# LED_Heart.net
KiCad netlist of a schematic drawn in EAGLE
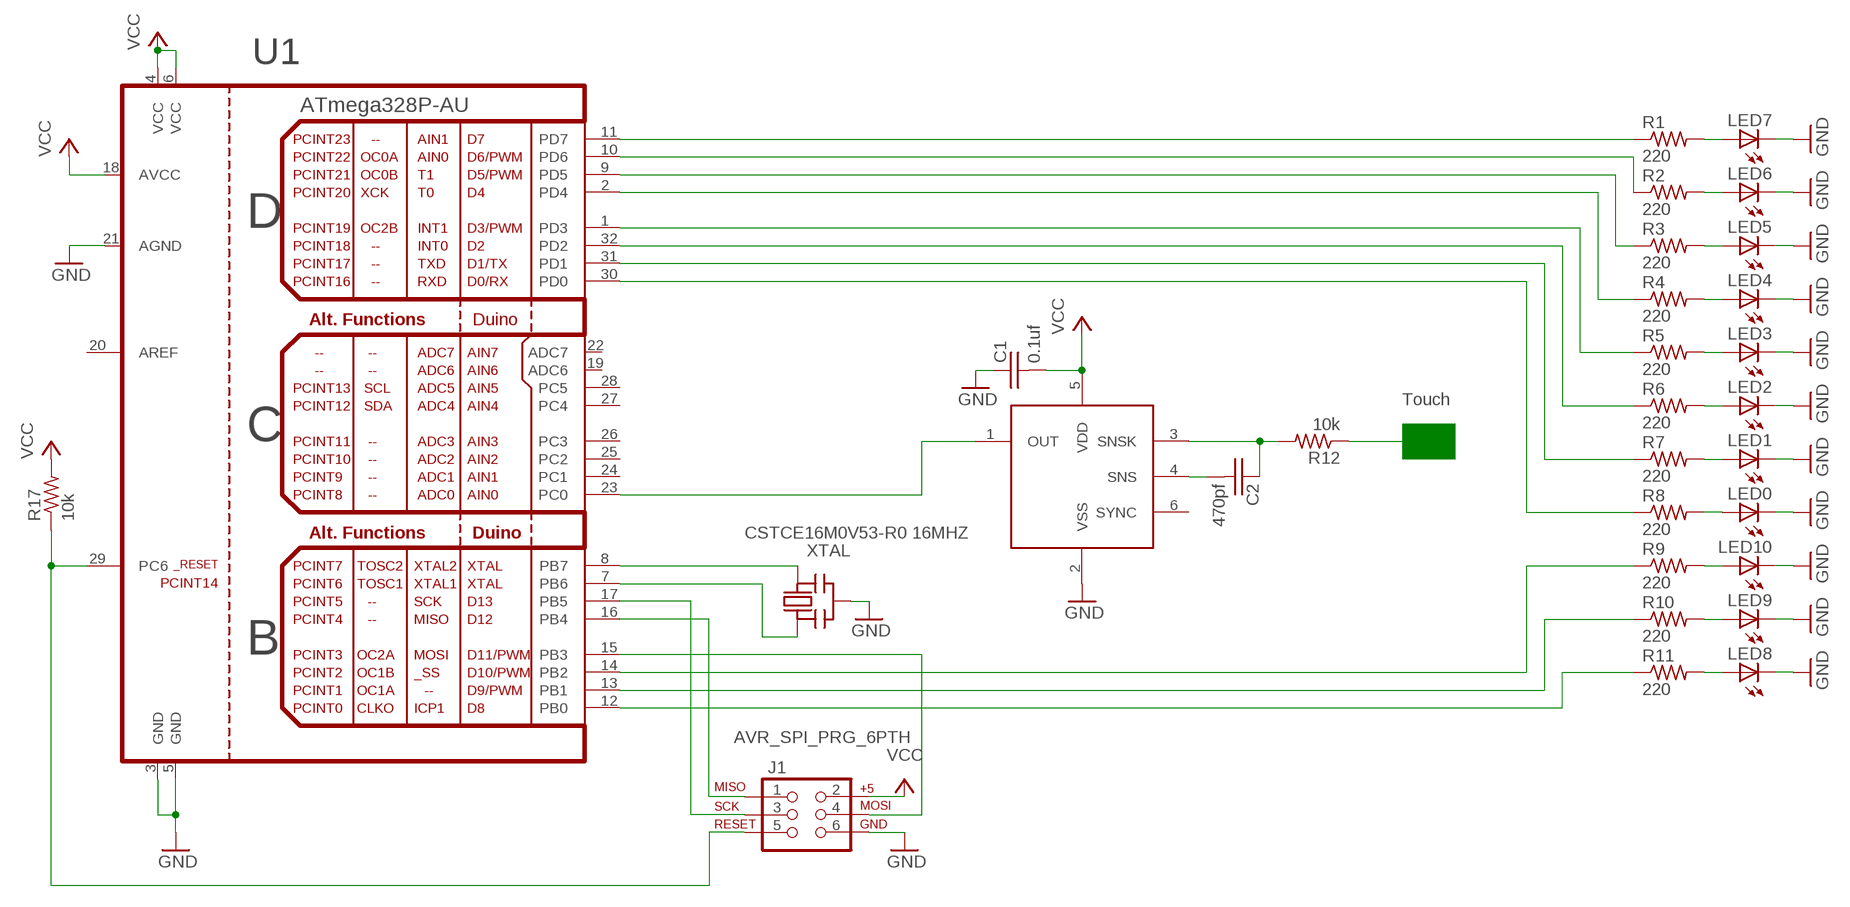
[diagram p0: schematic, sheet 1]

(export (version "E")
  (design (tool "Eeschema 10.0.6"))
  (components
    (comp (ref "C1")
      (value "0.1uf")
      (footprint "eagle-import:C0603")
      (libsource (lib "eagle-import") (part "C-USC0603"))
    )
    (comp (ref "C2")
      (value "470pf")
      (footprint "eagle-import:C0603")
      (libsource (lib "eagle-import") (part "C-USC0603"))
    )
    (comp (ref "J1")
      (value "AVR_SPI_PRG_6PTH")
      (footprint "eagle-import:2X3")
      (libsource (lib "eagle-import") (part "AVR_SPI_PRG_6PTH"))
    )
    (comp (ref "LED0")
      (value "LED0603")
      (footprint "eagle-import:LED-0603")
      (libsource (lib "eagle-import") (part "LED0603"))
    )
    (comp (ref "LED1")
      (value "LED0603")
      (footprint "eagle-import:LED-0603")
      (libsource (lib "eagle-import") (part "LED0603"))
    )
    (comp (ref "LED2")
      (value "LED0603")
      (footprint "eagle-import:LED-0603")
      (libsource (lib "eagle-import") (part "LED0603"))
    )
    (comp (ref "LED3")
      (value "LED0603")
      (footprint "eagle-import:LED-0603")
      (libsource (lib "eagle-import") (part "LED0603"))
    )
    (comp (ref "LED4")
      (value "LED0603")
      (footprint "eagle-import:LED-0603")
      (libsource (lib "eagle-import") (part "LED0603"))
    )
    (comp (ref "LED5")
      (value "LED0603")
      (footprint "eagle-import:LED-0603")
      (libsource (lib "eagle-import") (part "LED0603"))
    )
    (comp (ref "LED6")
      (value "LED0603")
      (footprint "eagle-import:LED-0603")
      (libsource (lib "eagle-import") (part "LED0603"))
    )
    (comp (ref "LED7")
      (value "LED0603")
      (footprint "eagle-import:LED-0603")
      (libsource (lib "eagle-import") (part "LED0603"))
    )
    (comp (ref "LED8")
      (value "LED0603")
      (footprint "eagle-import:LED-0603")
      (libsource (lib "eagle-import") (part "LED0603"))
    )
    (comp (ref "LED9")
      (value "LED0603")
      (footprint "eagle-import:LED-0603")
      (libsource (lib "eagle-import") (part "LED0603"))
    )
    (comp (ref "LED10")
      (value "LED0603")
      (footprint "eagle-import:LED-0603")
      (libsource (lib "eagle-import") (part "LED0603"))
    )
    (comp (ref "R1")
      (value "220")
      (footprint "eagle-import:R0402")
      (libsource (lib "eagle-import") (part "R-US_R0402"))
    )
    (comp (ref "R2")
      (value "220")
      (footprint "eagle-import:R0402")
      (libsource (lib "eagle-import") (part "R-US_R0402"))
    )
    (comp (ref "R3")
      (value "220")
      (footprint "eagle-import:R0402")
      (libsource (lib "eagle-import") (part "R-US_R0402"))
    )
    (comp (ref "R4")
      (value "220")
      (footprint "eagle-import:R0402")
      (libsource (lib "eagle-import") (part "R-US_R0402"))
    )
    (comp (ref "R5")
      (value "220")
      (footprint "eagle-import:R0402")
      (libsource (lib "eagle-import") (part "R-US_R0402"))
    )
    (comp (ref "R6")
      (value "220")
      (footprint "eagle-import:R0402")
      (libsource (lib "eagle-import") (part "R-US_R0402"))
    )
    (comp (ref "R7")
      (value "220")
      (footprint "eagle-import:R0402")
      (libsource (lib "eagle-import") (part "R-US_R0402"))
    )
    (comp (ref "R8")
      (value "220")
      (footprint "eagle-import:R0402")
      (libsource (lib "eagle-import") (part "R-US_R0402"))
    )
    (comp (ref "R9")
      (value "220")
      (footprint "eagle-import:R0402")
      (libsource (lib "eagle-import") (part "R-US_R0402"))
    )
    (comp (ref "R10")
      (value "220")
      (footprint "eagle-import:R0402")
      (libsource (lib "eagle-import") (part "R-US_R0402"))
    )
    (comp (ref "R11")
      (value "220")
      (footprint "eagle-import:R0402")
      (libsource (lib "eagle-import") (part "R-US_R0402"))
    )
    (comp (ref "R12")
      (value "10k")
      (footprint "eagle-import:R0402")
      (libsource (lib "eagle-import") (part "R-US_R0402"))
    )
    (comp (ref "R17")
      (value "10k")
      (footprint "eagle-import:R0402")
      (libsource (lib "eagle-import") (part "R-US_R0402"))
    )
    (comp (ref "U$1")
      (value "QT100")
      (footprint "eagle-import:SOT23-6")
      (libsource (lib "eagle-import") (part "QT100"))
    )
    (comp (ref "U1")
      (value "ATmega328P-AU")
      (footprint "eagle-import:TQFP-32-08")
      (libsource (lib "eagle-import") (part "ATMEGA328"))
    )
    (comp (ref "XTAL")
      (value "CSTCE16M0V53-R0 16MHZ")
      (footprint "eagle-import:CERM_OSC")
      (libsource (lib "eagle-import") (part "CERMOSCILL-THM"))
    )
  )
  (nets
    (net (code "1") (name "GND") (class "Default")
      (node (ref "C1") (pin "1") (pinfunction "1_1") (pintype "passive"))
      (node (ref "J1") (pin "6") (pinfunction "6_6") (pintype "passive"))
      (node (ref "LED0") (pin "C") (pinfunction "C_C") (pintype "passive"))
      (node (ref "LED1") (pin "C") (pinfunction "C_C") (pintype "passive"))
      (node (ref "LED10") (pin "C") (pinfunction "C_C") (pintype "passive"))
      (node (ref "LED2") (pin "C") (pinfunction "C_C") (pintype "passive"))
      (node (ref "LED3") (pin "C") (pinfunction "C_C") (pintype "passive"))
      (node (ref "LED4") (pin "C") (pinfunction "C_C") (pintype "passive"))
      (node (ref "LED5") (pin "C") (pinfunction "C_C") (pintype "passive"))
      (node (ref "LED6") (pin "C") (pinfunction "C_C") (pintype "passive"))
      (node (ref "LED7") (pin "C") (pinfunction "C_C") (pintype "passive"))
      (node (ref "LED8") (pin "C") (pinfunction "C_C") (pintype "passive"))
      (node (ref "LED9") (pin "C") (pinfunction "C_C") (pintype "passive"))
      (node (ref "U$1") (pin "2") (pinfunction "VSS_2") (pintype "bidirectional"))
      (node (ref "U1") (pin "21") (pinfunction "AGND_21") (pintype "power_in"))
      (node (ref "U1") (pin "3") (pinfunction "GND_3") (pintype "power_in"))
      (node (ref "U1") (pin "5") (pinfunction "GND_5") (pintype "power_in"))
      (node (ref "XTAL") (pin "P$2") (pinfunction "GND_P$2") (pintype "bidirectional"))
    )
    (net (code "2") (name "Net-(LED0-PadA)") (class "Default")
      (node (ref "LED0") (pin "A") (pinfunction "A_A") (pintype "passive"))
      (node (ref "R8") (pin "2") (pinfunction "2_2") (pintype "passive"))
    )
    (net (code "3") (name "Net-(LED1-PadA)") (class "Default")
      (node (ref "LED1") (pin "A") (pinfunction "A_A") (pintype "passive"))
      (node (ref "R7") (pin "2") (pinfunction "2_2") (pintype "passive"))
    )
    (net (code "4") (name "Net-(LED2-PadA)") (class "Default")
      (node (ref "LED2") (pin "A") (pinfunction "A_A") (pintype "passive"))
      (node (ref "R6") (pin "2") (pinfunction "2_2") (pintype "passive"))
    )
    (net (code "5") (name "Net-(LED3-PadA)") (class "Default")
      (node (ref "LED3") (pin "A") (pinfunction "A_A") (pintype "passive"))
      (node (ref "R5") (pin "2") (pinfunction "2_2") (pintype "passive"))
    )
    (net (code "6") (name "Net-(LED4-PadA)") (class "Default")
      (node (ref "LED4") (pin "A") (pinfunction "A_A") (pintype "passive"))
      (node (ref "R4") (pin "2") (pinfunction "2_2") (pintype "passive"))
    )
    (net (code "7") (name "Net-(LED5-PadA)") (class "Default")
      (node (ref "LED5") (pin "A") (pinfunction "A_A") (pintype "passive"))
      (node (ref "R3") (pin "2") (pinfunction "2_2") (pintype "passive"))
    )
    (net (code "8") (name "Net-(LED6-PadA)") (class "Default")
      (node (ref "LED6") (pin "A") (pinfunction "A_A") (pintype "passive"))
      (node (ref "R2") (pin "2") (pinfunction "2_2") (pintype "passive"))
    )
    (net (code "9") (name "Net-(LED7-PadA)") (class "Default")
      (node (ref "LED7") (pin "A") (pinfunction "A_A") (pintype "passive"))
      (node (ref "R1") (pin "2") (pinfunction "2_2") (pintype "passive"))
    )
    (net (code "10") (name "Net-(LED8-PadA)") (class "Default")
      (node (ref "LED8") (pin "A") (pinfunction "A_A") (pintype "passive"))
      (node (ref "R11") (pin "2") (pinfunction "2_2") (pintype "passive"))
    )
    (net (code "11") (name "Net-(LED9-PadA)") (class "Default")
      (node (ref "LED9") (pin "A") (pinfunction "A_A") (pintype "passive"))
      (node (ref "R10") (pin "2") (pinfunction "2_2") (pintype "passive"))
    )
    (net (code "12") (name "Net-(LED10-PadA)") (class "Default")
      (node (ref "LED10") (pin "A") (pinfunction "A_A") (pintype "passive"))
      (node (ref "R9") (pin "2") (pinfunction "2_2") (pintype "passive"))
    )
    (net (code "13") (name "Net-(U$1-OUT)") (class "Default")
      (node (ref "U$1") (pin "1") (pinfunction "OUT_1") (pintype "bidirectional"))
      (node (ref "U1") (pin "23") (pinfunction "PC0_23") (pintype "bidirectional"))
    )
    (net (code "14") (name "Net-(U$1-SNS)") (class "Default")
      (node (ref "C2") (pin "2") (pinfunction "2_2") (pintype "passive"))
      (node (ref "U$1") (pin "4") (pinfunction "SNS_4") (pintype "bidirectional"))
    )
    (net (code "15") (name "Net-(U$1-SNSK)") (class "Default")
      (node (ref "C2") (pin "1") (pinfunction "1_1") (pintype "passive"))
      (node (ref "R12") (pin "2") (pinfunction "2_2") (pintype "passive"))
      (node (ref "U$1") (pin "3") (pinfunction "SNSK_3") (pintype "bidirectional"))
    )
    (net (code "16") (name "Net-(U1-PB0)") (class "Default")
      (node (ref "R11") (pin "1") (pinfunction "1_1") (pintype "passive"))
      (node (ref "U1") (pin "12") (pinfunction "PB0_12") (pintype "bidirectional"))
    )
    (net (code "17") (name "Net-(U1-PB1)") (class "Default")
      (node (ref "R10") (pin "1") (pinfunction "1_1") (pintype "passive"))
      (node (ref "U1") (pin "13") (pinfunction "PB1_13") (pintype "bidirectional"))
    )
    (net (code "18") (name "Net-(U1-PB2)") (class "Default")
      (node (ref "R9") (pin "1") (pinfunction "1_1") (pintype "passive"))
      (node (ref "U1") (pin "14") (pinfunction "PB2_14") (pintype "bidirectional"))
    )
    (net (code "19") (name "Net-(U1-PB3)") (class "Default")
      (node (ref "J1") (pin "4") (pinfunction "4_4") (pintype "passive"))
      (node (ref "U1") (pin "15") (pinfunction "PB3_15") (pintype "bidirectional"))
    )
    (net (code "20") (name "Net-(U1-PB4)") (class "Default")
      (node (ref "J1") (pin "1") (pinfunction "1_1") (pintype "passive"))
      (node (ref "U1") (pin "16") (pinfunction "PB4_16") (pintype "bidirectional"))
    )
    (net (code "21") (name "Net-(U1-PB5)") (class "Default")
      (node (ref "J1") (pin "3") (pinfunction "3_3") (pintype "passive"))
      (node (ref "U1") (pin "17") (pinfunction "PB5_17") (pintype "bidirectional"))
    )
    (net (code "22") (name "Net-(U1-PB6)") (class "Default")
      (node (ref "U1") (pin "7") (pinfunction "PB6_7") (pintype "bidirectional"))
      (node (ref "XTAL") (pin "P$1") (pinfunction "IN_P$1") (pintype "bidirectional"))
    )
    (net (code "23") (name "Net-(U1-PB7)") (class "Default")
      (node (ref "U1") (pin "8") (pinfunction "PB7_8") (pintype "bidirectional"))
      (node (ref "XTAL") (pin "P$3") (pinfunction "OUT_P$3") (pintype "bidirectional"))
    )
    (net (code "24") (name "Net-(U1-PC6)") (class "Default")
      (node (ref "J1") (pin "5") (pinfunction "5_5") (pintype "passive"))
      (node (ref "R17") (pin "1") (pinfunction "1_1") (pintype "passive"))
      (node (ref "U1") (pin "29") (pinfunction "PC6_29") (pintype "bidirectional"))
    )
    (net (code "25") (name "Net-(U1-PD0)") (class "Default")
      (node (ref "R8") (pin "1") (pinfunction "1_1") (pintype "passive"))
      (node (ref "U1") (pin "30") (pinfunction "PD0_30") (pintype "bidirectional"))
    )
    (net (code "26") (name "Net-(U1-PD1)") (class "Default")
      (node (ref "R7") (pin "1") (pinfunction "1_1") (pintype "passive"))
      (node (ref "U1") (pin "31") (pinfunction "PD1_31") (pintype "bidirectional"))
    )
    (net (code "27") (name "Net-(U1-PD2)") (class "Default")
      (node (ref "R6") (pin "1") (pinfunction "1_1") (pintype "passive"))
      (node (ref "U1") (pin "32") (pinfunction "PD2_32") (pintype "bidirectional"))
    )
    (net (code "28") (name "Net-(U1-PD3)") (class "Default")
      (node (ref "R5") (pin "1") (pinfunction "1_1") (pintype "passive"))
      (node (ref "U1") (pin "1") (pinfunction "PD3_1") (pintype "bidirectional"))
    )
    (net (code "29") (name "Net-(U1-PD4)") (class "Default")
      (node (ref "R4") (pin "1") (pinfunction "1_1") (pintype "passive"))
      (node (ref "U1") (pin "2") (pinfunction "PD4_2") (pintype "bidirectional"))
    )
    (net (code "30") (name "Net-(U1-PD5)") (class "Default")
      (node (ref "R3") (pin "1") (pinfunction "1_1") (pintype "passive"))
      (node (ref "U1") (pin "9") (pinfunction "PD5_9") (pintype "bidirectional"))
    )
    (net (code "31") (name "Net-(U1-PD6)") (class "Default")
      (node (ref "R2") (pin "1") (pinfunction "1_1") (pintype "passive"))
      (node (ref "U1") (pin "10") (pinfunction "PD6_10") (pintype "bidirectional"))
    )
    (net (code "32") (name "Net-(U1-PD7)") (class "Default")
      (node (ref "R1") (pin "1") (pinfunction "1_1") (pintype "passive"))
      (node (ref "U1") (pin "11") (pinfunction "PD7_11") (pintype "bidirectional"))
    )
    (net (code "33") (name "VCC") (class "Default")
      (node (ref "C1") (pin "2") (pinfunction "2_2") (pintype "passive"))
      (node (ref "J1") (pin "2") (pinfunction "2_2") (pintype "passive"))
      (node (ref "R17") (pin "2") (pinfunction "2_2") (pintype "passive"))
      (node (ref "U$1") (pin "5") (pinfunction "VDD_5") (pintype "bidirectional"))
      (node (ref "U1") (pin "18") (pinfunction "AVCC_18") (pintype "power_in"))
      (node (ref "U1") (pin "4") (pinfunction "VCC_4") (pintype "power_in"))
      (node (ref "U1") (pin "6") (pinfunction "VCC_6") (pintype "power_in"))
    )
    (net (code "34") (name "unconnected-(R12-Pad1)") (class "Default")
      (node (ref "R12") (pin "1") (pinfunction "1_1") (pintype "passive"))
    )
    (net (code "35") (name "unconnected-(U$1-SYNC-Pad6)") (class "Default")
      (node (ref "U$1") (pin "6") (pinfunction "SYNC_6") (pintype "bidirectional"))
    )
    (net (code "36") (name "unconnected-(U1-ADC6-Pad19)") (class "Default")
      (node (ref "U1") (pin "19") (pinfunction "ADC6_19") (pintype "bidirectional"))
    )
    (net (code "37") (name "unconnected-(U1-ADC7-Pad22)") (class "Default")
      (node (ref "U1") (pin "22") (pinfunction "ADC7_22") (pintype "bidirectional"))
    )
    (net (code "38") (name "unconnected-(U1-AREF-Pad20)") (class "Default")
      (node (ref "U1") (pin "20") (pinfunction "AREF_20") (pintype "input"))
    )
    (net (code "39") (name "unconnected-(U1-PC1-Pad24)") (class "Default")
      (node (ref "U1") (pin "24") (pinfunction "PC1_24") (pintype "bidirectional"))
    )
    (net (code "40") (name "unconnected-(U1-PC2-Pad25)") (class "Default")
      (node (ref "U1") (pin "25") (pinfunction "PC2_25") (pintype "bidirectional"))
    )
    (net (code "41") (name "unconnected-(U1-PC3-Pad26)") (class "Default")
      (node (ref "U1") (pin "26") (pinfunction "PC3_26") (pintype "bidirectional"))
    )
    (net (code "42") (name "unconnected-(U1-PC4-Pad27)") (class "Default")
      (node (ref "U1") (pin "27") (pinfunction "PC4_27") (pintype "bidirectional"))
    )
    (net (code "43") (name "unconnected-(U1-PC5-Pad28)") (class "Default")
      (node (ref "U1") (pin "28") (pinfunction "PC5_28") (pintype "bidirectional"))
    )
  )
)
